# main.net
KiCad netlist of a schematic drawn in Altium Designer
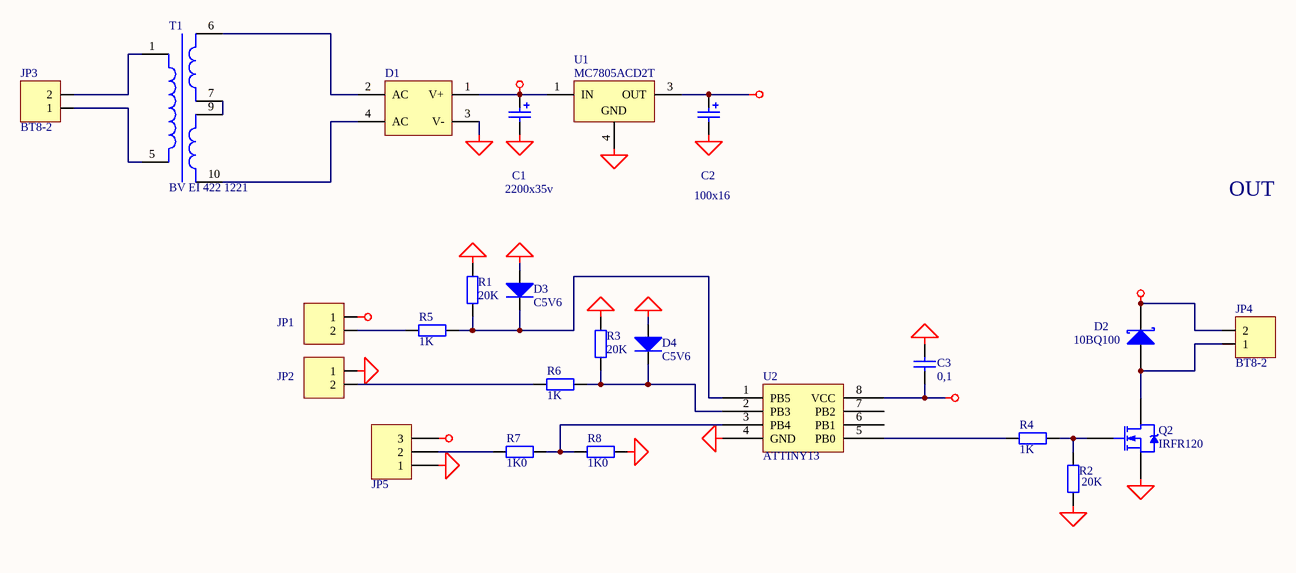
[diagram p0: main.SCHDOC]

(export (version "E")
  (design (tool "Eeschema 10.0.6"))
  (components
    (comp (ref "C1")
      (value "2200x35v")
      (footprint "el8_L")
      (description "Polarized Capacitor (Radial)")
      (fields (field (name "MANUFACTURER") "Generic Components") (field (name "PUBLISHER") "Altium Limited"))
      (libsource (lib "BUF") (part "Cap Pol1"))
    )
    (comp (ref "C2")
      (value "100x16")
      (footprint "el3_L")
      (description "Polarized Capacitor (Radial)")
      (fields (field (name "MANUFACTURER") "Generic Components") (field (name "PUBLISHER") "Altium Limited"))
      (libsource (lib "BUF") (part "Cap Pol"))
    )
    (comp (ref "C3")
      (value "Cap Semi")
      (footprint "_1206")
      (description "Capacitor (Semiconductor SIM Model)")
      (fields
        (field (name "MANUFACTURER") "Generic Components")
        (field (name "ALTIUM_VALUE") "0,1")
        (field (name "PUBLISHER") "Altium Limited")
      )
      (libsource (lib "Miscellaneous Devices") (part "Cap Semi"))
    )
    (comp (ref "D1")
      (value "Bridge2")
      (footprint "KBU8M_L")
      (description "Diode Bridge")
      (fields (field (name "MANUFACTURER") "Generic Components") (field (name "PUBLISHER") "Altium Limited"))
      (libsource (lib "BUF") (part "Bridge2"))
    )
    (comp (ref "D2")
      (value "10BQ100")
      (footprint "DSO-C2/X2.3")
      (description "Schottky Rectifier")
      (fields
        (field (name "MANUFACTURER") "International Rectifier")
        (field (name "PUBLISHER") "Altium Limited")
      )
      (libsource (lib "IR Discrete Diode") (part "10BQ015"))
    )
    (comp (ref "D3")
      (value "C5V6")
      (footprint "_1206d")
      (description "Default Diode")
      (fields (field (name "MANUFACTURER") "Generic Components") (field (name "PUBLISHER") "Altium Limited"))
      (libsource (lib "PAL") (part "Diode"))
    )
    (comp (ref "D4")
      (value "C5V6")
      (footprint "_1206d")
      (description "Default Diode")
      (fields (field (name "MANUFACTURER") "Generic Components") (field (name "PUBLISHER") "Altium Limited"))
      (libsource (lib "PAL") (part "Diode"))
    )
    (comp (ref "JP1")
      (value "BT5-2")
      (footprint "BT5-2_L")
      (description "Header, 3-Pin")
      (fields (field (name "MANUFACTURER") "Generic Components") (field (name "PUBLISHER") "Altium Limited"))
      (libsource (lib "") (part "BT5-2_1"))
    )
    (comp (ref "JP2")
      (value "BT5-2")
      (footprint "BT5-2_L")
      (description "Header, 3-Pin")
      (fields (field (name "MANUFACTURER") "Generic Components") (field (name "PUBLISHER") "Altium Limited"))
      (libsource (lib "") (part "BT5-2_1"))
    )
    (comp (ref "JP3")
      (value "BT8-2")
      (footprint "BT8-2_L")
      (description "Header, 3-Pin")
      (fields (field (name "MANUFACTURER") "Generic Components") (field (name "PUBLISHER") "Altium Limited"))
      (libsource (lib "") (part "BT5-2_2"))
    )
    (comp (ref "JP4")
      (value "BT8-2")
      (footprint "BT8-2_L")
      (description "Header, 3-Pin")
      (fields (field (name "MANUFACTURER") "Generic Components") (field (name "PUBLISHER") "Altium Limited"))
      (libsource (lib "PAL") (part "BT5-2"))
    )
    (comp (ref "JP5")
      (value "Header 3")
      (footprint "BT5-3_L")
      (description "Header, 3-Pin")
      (fields (field (name "MANUFACTURER") "Generic Components") (field (name "PUBLISHER") "Altium Limited"))
      (libsource (lib "Miscellaneous Connectors") (part "Header 3"))
    )
    (comp (ref "Q2")
      (value "IRFR120")
      (footprint "SIP-G3")
      (description "HEXFET N-Channel Power MOSFET")
      (fields
        (field (name "MANUFACTURER") "International Rectifier")
        (field (name "PUBLISHER") "Altium Limited")
      )
      (libsource (lib "IR Discrete MOSFET") (part "IRFR120"))
    )
    (comp (ref "R1")
      (value "20K")
      (footprint "_1206")
      (description "Resistor")
      (fields (field (name "MANUFACTURER") "Generic Components") (field (name "PUBLISHER") "Altium Limited"))
      (libsource (lib "Miscellaneous Devices") (part "Res2"))
    )
    (comp (ref "R2")
      (value "20K")
      (footprint "_1206")
      (description "Resistor")
      (fields (field (name "MANUFACTURER") "Generic Components") (field (name "PUBLISHER") "Altium Limited"))
      (libsource (lib "") (part "Res2_1"))
    )
    (comp (ref "R3")
      (value "20K")
      (footprint "_1206")
      (description "Resistor")
      (fields (field (name "MANUFACTURER") "Generic Components") (field (name "PUBLISHER") "Altium Limited"))
      (libsource (lib "Miscellaneous Devices") (part "Res2"))
    )
    (comp (ref "R4")
      (value "1K")
      (footprint "_1206")
      (description "Resistor")
      (fields (field (name "MANUFACTURER") "Generic Components") (field (name "PUBLISHER") "Altium Limited"))
      (libsource (lib "Miscellaneous Devices") (part "Res2"))
    )
    (comp (ref "R5")
      (value "1K")
      (footprint "_1206")
      (description "Resistor")
      (fields (field (name "MANUFACTURER") "Generic Components") (field (name "PUBLISHER") "Altium Limited"))
      (libsource (lib "") (part "Res2_2"))
    )
    (comp (ref "R6")
      (value "1K")
      (footprint "_1206")
      (description "Resistor")
      (fields (field (name "MANUFACTURER") "Generic Components") (field (name "PUBLISHER") "Altium Limited"))
      (libsource (lib "") (part "Res2_2"))
    )
    (comp (ref "R7")
      (value "1K0")
      (footprint "_1206")
      (description "Resistor")
      (fields (field (name "MANUFACTURER") "Generic Components") (field (name "PUBLISHER") "Altium Limited"))
      (libsource (lib "") (part "Res2_1"))
    )
    (comp (ref "R8")
      (value "1K0")
      (footprint "_1206")
      (description "Resistor")
      (fields (field (name "MANUFACTURER") "Generic Components") (field (name "PUBLISHER") "Altium Limited"))
      (libsource (lib "") (part "Res2_1"))
    )
    (comp (ref "T1")
      (value "BV EI 422 1221")
      (footprint "BV EI 304 2840_L")
      (fields (field (name "MANUFACTURER") "Generic Components") (field (name "PUBLISHER") "Altium Limited"))
      (libsource (lib "PAL") (part "BV EI 422 1221"))
    )
    (comp (ref "U1")
      (value "MC7805ACD2T")
      (footprint "D2PAKTO220_L")
      (description "Three-Terminal Positive Voltage Regulator")
      (fields (field (name "MANUFACTURER") "ON Semiconductor") (field (name "PUBLISHER") "Altium Limited"))
      (libsource (lib "ON Semi Power Mgt Voltage Regulator") (part "MC7805ACD2T"))
    )
    (comp (ref "U2") (value "ATTINY13") (footprint "DIP-8") (libsource (lib "PAL") (part "ATTINY13")))
  )
  (nets
    (net (code "1") (name "+5v") (class "Default")
      (node (ref "C2") (pin "1") (pinfunction "1_1") (pintype "passive"))
      (node (ref "C3") (pin "2") (pinfunction "2_2") (pintype "passive"))
      (node (ref "JP5") (pin "3") (pinfunction "3_3") (pintype "passive"))
      (node (ref "U1") (pin "3") (pinfunction "OUT_3") (pintype "power_in"))
      (node (ref "U2") (pin "8") (pinfunction "VCC_8") (pintype "passive"))
    )
    (net (code "2") (name "+24v") (class "Default")
      (node (ref "C1") (pin "1") (pinfunction "1_1") (pintype "passive"))
      (node (ref "D1") (pin "1") (pinfunction "V+_1") (pintype "passive"))
      (node (ref "D2") (pin "2") (pinfunction "K_2") (pintype "passive"))
      (node (ref "JP1") (pin "1") (pinfunction "1_1") (pintype "passive"))
      (node (ref "JP4") (pin "2") (pinfunction "2_2") (pintype "passive"))
      (node (ref "U1") (pin "1") (pinfunction "IN_1") (pintype "power_in"))
    )
    (net (code "3") (name "GND") (class "Default")
      (node (ref "C1") (pin "2") (pinfunction "2_2") (pintype "passive"))
      (node (ref "C2") (pin "2") (pinfunction "2_2") (pintype "passive"))
      (node (ref "C3") (pin "1") (pinfunction "1_1") (pintype "passive"))
      (node (ref "D1") (pin "3") (pinfunction "V-_3") (pintype "passive"))
      (node (ref "D3") (pin "1") (pinfunction "A_1") (pintype "passive"))
      (node (ref "D4") (pin "1") (pinfunction "A_1") (pintype "passive"))
      (node (ref "JP2") (pin "1") (pinfunction "1_1") (pintype "passive"))
      (node (ref "JP5") (pin "1") (pinfunction "1_1") (pintype "passive"))
      (node (ref "Q2") (pin "3") (pinfunction "S_3") (pintype "passive"))
      (node (ref "R1") (pin "2") (pinfunction "2_2") (pintype "passive"))
      (node (ref "R2") (pin "2") (pinfunction "2_2") (pintype "passive"))
      (node (ref "R3") (pin "2") (pinfunction "2_2") (pintype "passive"))
      (node (ref "R8") (pin "1") (pinfunction "1_1") (pintype "passive"))
      (node (ref "U1") (pin "4") (pinfunction "GND_4") (pintype "power_in"))
      (node (ref "U2") (pin "4") (pinfunction "GND_4") (pintype "passive"))
    )
    (net (code "4") (name "Net-(D1-AC-Pad2)") (class "Default")
      (node (ref "D1") (pin "2") (pinfunction "AC_2") (pintype "passive"))
      (node (ref "T1") (pin "6") (pinfunction "Sec1+_6") (pintype "passive"))
    )
    (net (code "5") (name "Net-(D1-AC-Pad4)") (class "Default")
      (node (ref "D1") (pin "4") (pinfunction "AC_4") (pintype "passive"))
      (node (ref "T1") (pin "10") (pinfunction "Sec1-_10") (pintype "passive"))
    )
    (net (code "6") (name "Net-(D2-A)") (class "Default")
      (node (ref "D2") (pin "1") (pinfunction "A_1") (pintype "passive"))
      (node (ref "JP4") (pin "1") (pinfunction "1_1") (pintype "passive"))
      (node (ref "Q2") (pin "4") (pinfunction "D_4") (pintype "passive"))
    )
    (net (code "7") (name "Net-(D3-K)") (class "Default")
      (node (ref "D3") (pin "2") (pinfunction "K_2") (pintype "passive"))
      (node (ref "R1") (pin "1") (pinfunction "1_1") (pintype "passive"))
      (node (ref "R5") (pin "2") (pinfunction "2_2") (pintype "passive"))
      (node (ref "U2") (pin "1") (pinfunction "PB5_1") (pintype "passive"))
    )
    (net (code "8") (name "Net-(D4-K)") (class "Default")
      (node (ref "D4") (pin "2") (pinfunction "K_2") (pintype "passive"))
      (node (ref "R3") (pin "1") (pinfunction "1_1") (pintype "passive"))
      (node (ref "R6") (pin "2") (pinfunction "2_2") (pintype "passive"))
      (node (ref "U2") (pin "2") (pinfunction "PB3_2") (pintype "passive"))
    )
    (net (code "9") (name "Net-(JP1-Pad2)") (class "Default")
      (node (ref "JP1") (pin "2") (pinfunction "2_2") (pintype "passive"))
      (node (ref "R5") (pin "1") (pinfunction "1_1") (pintype "passive"))
    )
    (net (code "10") (name "Net-(JP2-Pad2)") (class "Default")
      (node (ref "JP2") (pin "2") (pinfunction "2_2") (pintype "passive"))
      (node (ref "R6") (pin "1") (pinfunction "1_1") (pintype "passive"))
    )
    (net (code "11") (name "Net-(JP5-Pad2)") (class "Default")
      (node (ref "JP5") (pin "2") (pinfunction "2_2") (pintype "passive"))
      (node (ref "R7") (pin "2") (pinfunction "2_2") (pintype "passive"))
    )
    (net (code "12") (name "Net-(Q2-G)") (class "Default")
      (node (ref "Q2") (pin "1") (pinfunction "G_1") (pintype "passive"))
      (node (ref "R2") (pin "1") (pinfunction "1_1") (pintype "passive"))
      (node (ref "R4") (pin "2") (pinfunction "2_2") (pintype "passive"))
    )
    (net (code "13") (name "Net-(T1-Pri+)") (class "Default")
      (node (ref "JP3") (pin "2") (pinfunction "2_2") (pintype "passive"))
      (node (ref "T1") (pin "1") (pinfunction "Pri+_1") (pintype "passive"))
    )
    (net (code "14") (name "Net-(T1-Pri-)") (class "Default")
      (node (ref "JP3") (pin "1") (pinfunction "1_1") (pintype "passive"))
      (node (ref "T1") (pin "5") (pinfunction "Pri-_5") (pintype "passive"))
    )
    (net (code "15") (name "Net-(T1-Sec1+-Pad9)") (class "Default")
      (node (ref "T1") (pin "7") (pinfunction "Sec1-_7") (pintype "passive"))
      (node (ref "T1") (pin "9") (pinfunction "Sec1+_9") (pintype "passive"))
    )
    (net (code "16") (name "Net-(U2-PB0)") (class "Default")
      (node (ref "R4") (pin "1") (pinfunction "1_1") (pintype "passive"))
      (node (ref "U2") (pin "5") (pinfunction "PB0_5") (pintype "passive"))
    )
    (net (code "17") (name "Net-(U2-PB4)") (class "Default")
      (node (ref "R7") (pin "1") (pinfunction "1_1") (pintype "passive"))
      (node (ref "R8") (pin "2") (pinfunction "2_2") (pintype "passive"))
      (node (ref "U2") (pin "3") (pinfunction "PB4_3") (pintype "passive"))
    )
    (net (code "18") (name "unconnected-(U2-PB1-Pad6)") (class "Default")
      (node (ref "U2") (pin "6") (pinfunction "PB1_6") (pintype "passive"))
    )
    (net (code "19") (name "unconnected-(U2-PB2-Pad7)") (class "Default")
      (node (ref "U2") (pin "7") (pinfunction "PB2_7") (pintype "passive"))
    )
  )
)
